# combo-03_2.net
KiCad netlist of a schematic drawn in EAGLE
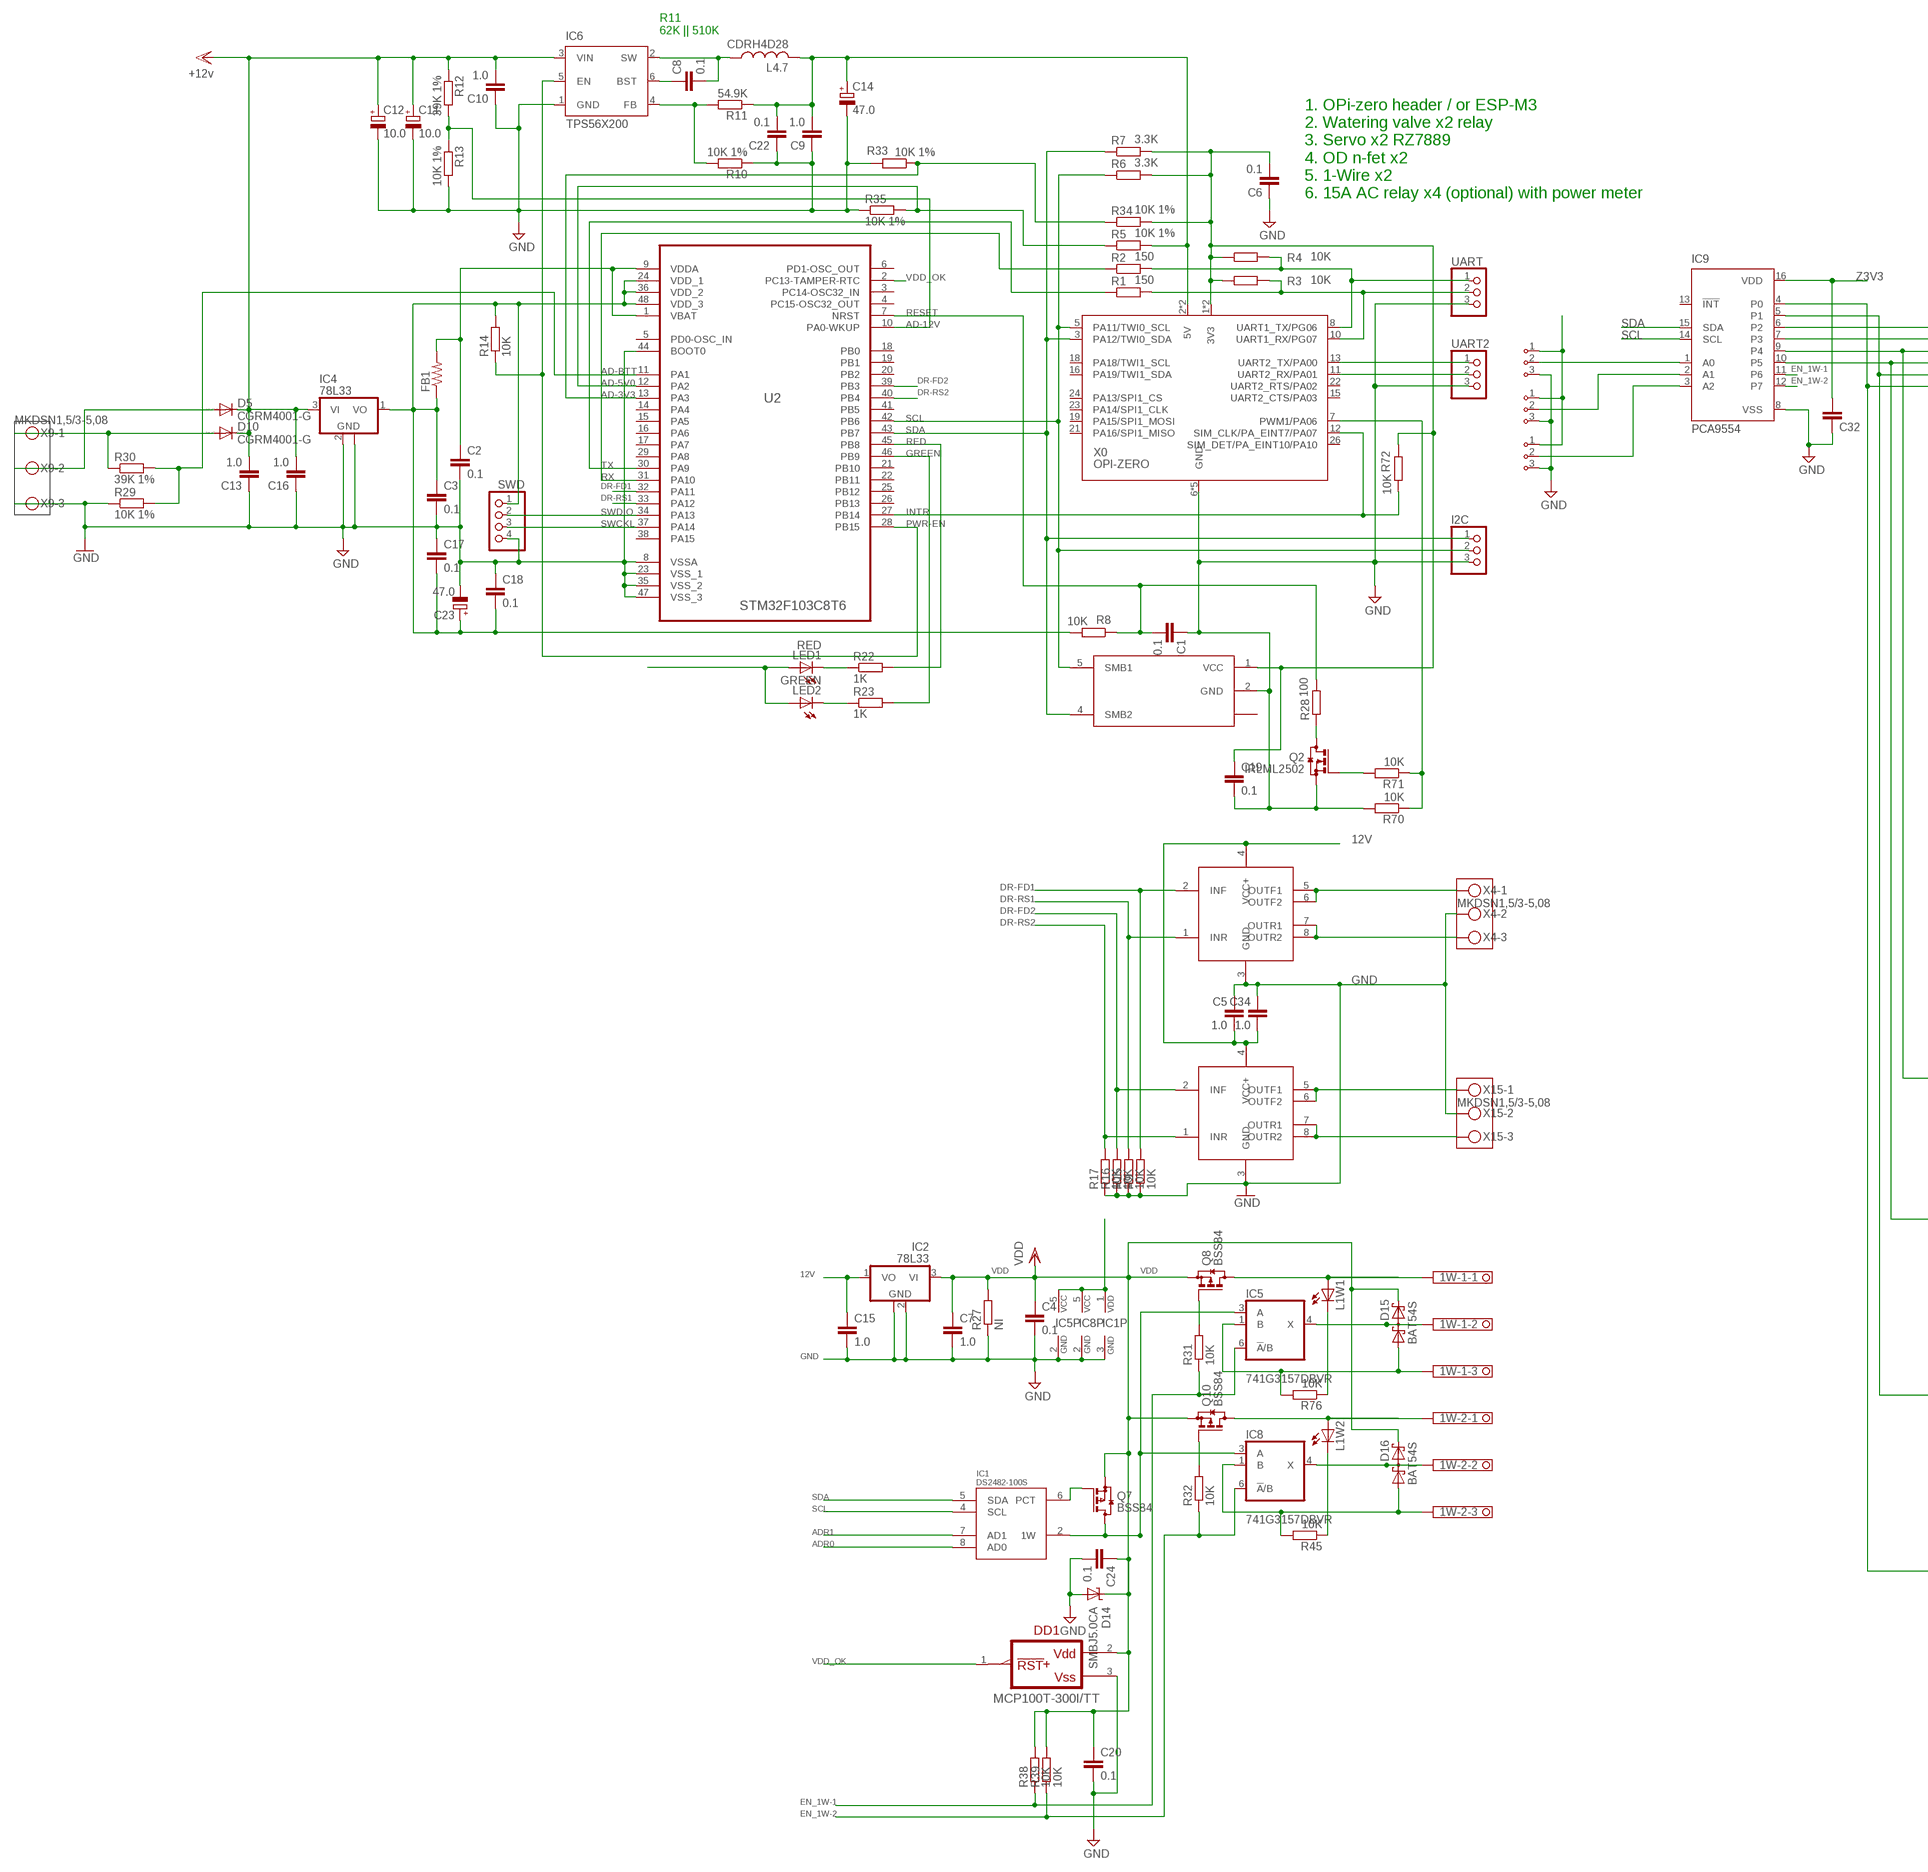
[diagram p0: schematic, sheet 1, part 1 of 2]
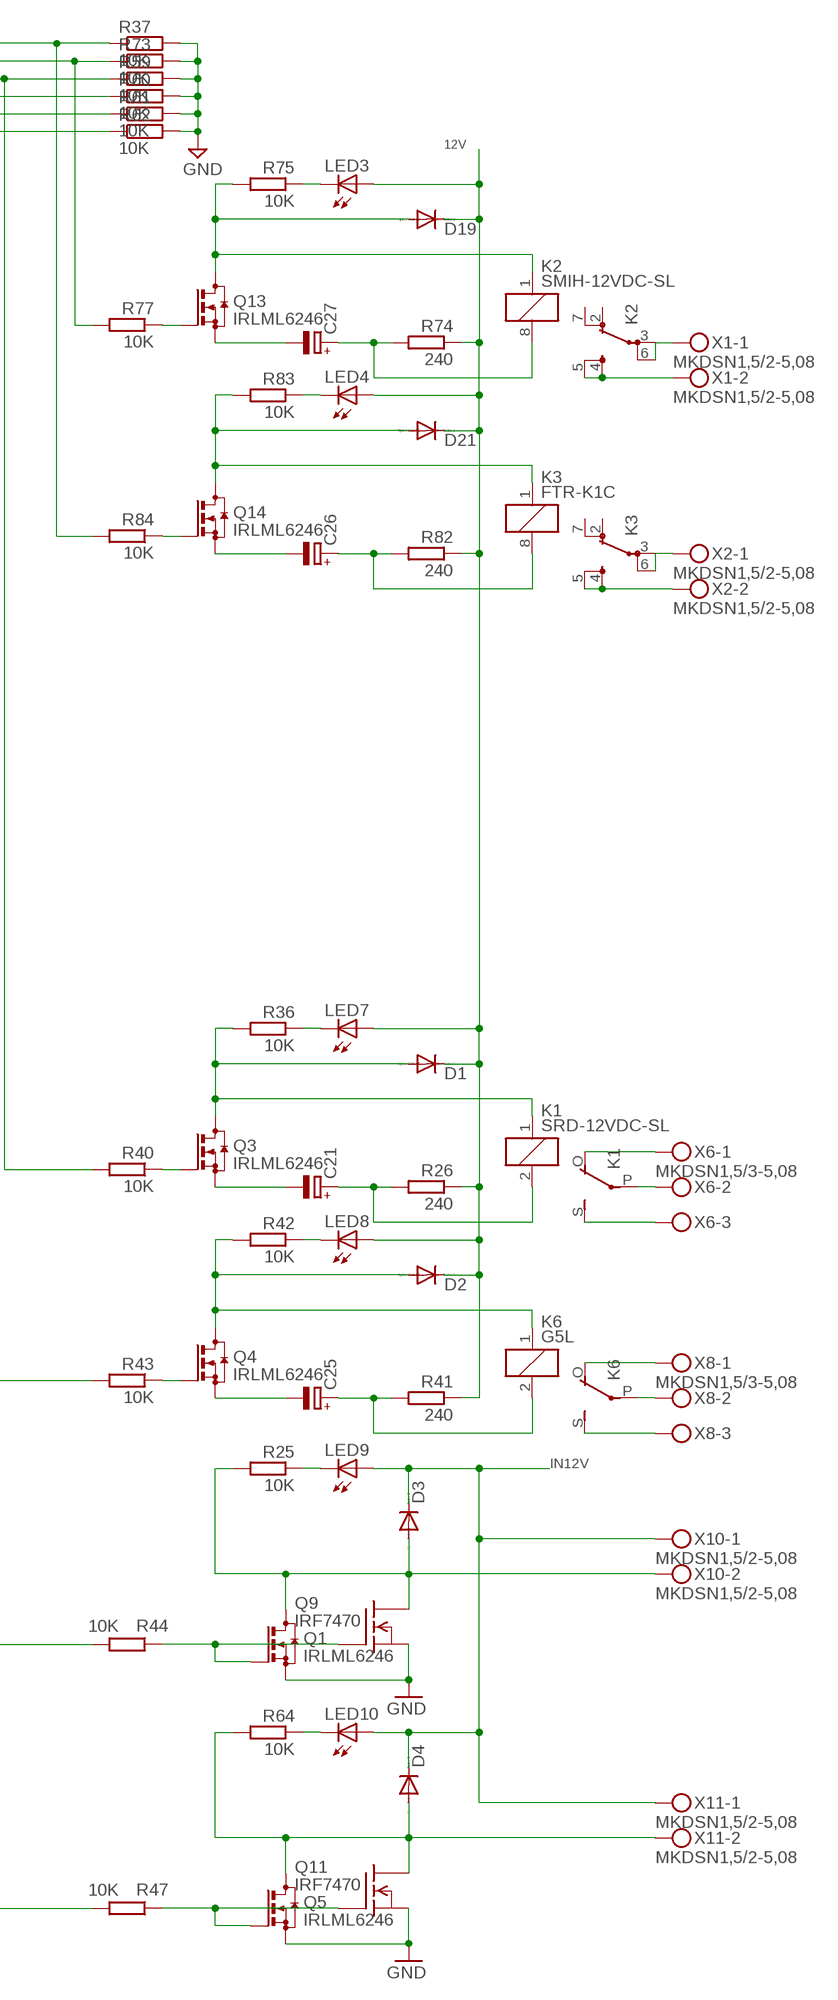
[diagram p1: schematic, sheet 1, part 2 of 2]

(export (version "E")
  (design (tool "Eeschema 10.0.6"))
  (components
    (comp (ref "1W-1")
      (value "1751251")
      (footprint "eagle-import:1751251")
      (libsource (lib "eagle-import") (part "1751251"))
    )
    (comp (ref "1W-2")
      (value "1751251")
      (footprint "eagle-import:1751251")
      (libsource (lib "eagle-import") (part "1751251"))
    )
    (comp (ref "A0")
      (value "ADDR3PIN0603")
      (footprint "eagle-import:0603-3PIN")
      (libsource (lib "eagle-import") (part "ADDR3PIN0603"))
    )
    (comp (ref "A1")
      (value "ADDR3PIN0603")
      (footprint "eagle-import:0603-3PIN")
      (libsource (lib "eagle-import") (part "ADDR3PIN0603"))
    )
    (comp (ref "A2")
      (value "ADDR3PIN0603")
      (footprint "eagle-import:0603-3PIN")
      (libsource (lib "eagle-import") (part "ADDR3PIN0603"))
    )
    (comp (ref "C1")
      (value "0.1")
      (footprint "eagle-import:C0603")
      (libsource (lib "eagle-import") (part "C-EUC0603"))
    )
    (comp (ref "C2")
      (value "0.1")
      (footprint "eagle-import:C0603")
      (libsource (lib "eagle-import") (part "C-EUC0603"))
    )
    (comp (ref "C3")
      (value "0.1")
      (footprint "eagle-import:C0603")
      (libsource (lib "eagle-import") (part "C-EUC0603"))
    )
    (comp (ref "C4")
      (value "0.1")
      (footprint "eagle-import:C0603")
      (libsource (lib "eagle-import") (part "C-EUC0603"))
    )
    (comp (ref "C5")
      (value "1.0")
      (footprint "eagle-import:C0805")
      (libsource (lib "eagle-import") (part "C-EUC0805"))
    )
    (comp (ref "C6")
      (value "0.1")
      (footprint "eagle-import:C0805")
      (libsource (lib "eagle-import") (part "C-EUC0805"))
    )
    (comp (ref "C7")
      (value "1.0")
      (footprint "eagle-import:C0805")
      (libsource (lib "eagle-import") (part "C-EUC0805"))
    )
    (comp (ref "C8")
      (value "0.1")
      (footprint "eagle-import:C0805")
      (libsource (lib "eagle-import") (part "C-EUC0805"))
    )
    (comp (ref "C9")
      (value "1.0")
      (footprint "eagle-import:C0805")
      (libsource (lib "eagle-import") (part "C-EUC0805"))
    )
    (comp (ref "C10")
      (value "1.0")
      (footprint "eagle-import:C1206")
      (libsource (lib "eagle-import") (part "C-EUC1206"))
    )
    (comp (ref "C11")
      (value "10.0")
      (footprint "eagle-import:C_6032-28R")
      (libsource (lib "eagle-import") (part "CPOL-EUC/6032-28R"))
    )
    (comp (ref "C12")
      (value "10.0")
      (footprint "eagle-import:C_6032-28R")
      (libsource (lib "eagle-import") (part "CPOL-EUC/6032-28R"))
    )
    (comp (ref "C13")
      (value "1.0")
      (footprint "eagle-import:C1206")
      (libsource (lib "eagle-import") (part "C-EUC1206"))
    )
    (comp (ref "C14")
      (value "47.0")
      (footprint "eagle-import:B_3528-21R")
      (libsource (lib "eagle-import") (part "CPOL-EUB/3528-21R"))
    )
    (comp (ref "C15")
      (value "1.0")
      (footprint "eagle-import:C0805")
      (libsource (lib "eagle-import") (part "C-EUC0805"))
    )
    (comp (ref "C16")
      (value "1.0")
      (footprint "eagle-import:C1206")
      (libsource (lib "eagle-import") (part "C-EUC1206"))
    )
    (comp (ref "C17")
      (value "0.1")
      (footprint "eagle-import:C0603")
      (libsource (lib "eagle-import") (part "C-EUC0603"))
    )
    (comp (ref "C18")
      (value "0.1")
      (footprint "eagle-import:C0603")
      (libsource (lib "eagle-import") (part "C-EUC0603"))
    )
    (comp (ref "C19")
      (value "0.1")
      (footprint "eagle-import:C0603")
      (libsource (lib "eagle-import") (part "C-EUC0603"))
    )
    (comp (ref "C20")
      (value "0.1")
      (footprint "eagle-import:C0603")
      (libsource (lib "eagle-import") (part "C-EUC0603"))
    )
    (comp (ref "C21")
      (value "CPOL-EUE3.5-8")
      (footprint "eagle-import:E3,5-8")
      (libsource (lib "eagle-import") (part "CPOL-EUE3.5-8"))
    )
    (comp (ref "C22")
      (value "0.1")
      (footprint "eagle-import:C0805")
      (libsource (lib "eagle-import") (part "C-EUC0805"))
    )
    (comp (ref "C23")
      (value "47.0")
      (footprint "eagle-import:B_3528-21R")
      (libsource (lib "eagle-import") (part "CPOL-EUB/3528-21R"))
    )
    (comp (ref "C24")
      (value "0.1")
      (footprint "eagle-import:C0603")
      (libsource (lib "eagle-import") (part "C-EUC0603"))
    )
    (comp (ref "C25")
      (value "CPOL-EUE3.5-8")
      (footprint "eagle-import:E3,5-8")
      (libsource (lib "eagle-import") (part "CPOL-EUE3.5-8"))
    )
    (comp (ref "C26")
      (value "CPOL-EUE3.5-8")
      (footprint "eagle-import:E3,5-8")
      (libsource (lib "eagle-import") (part "CPOL-EUE3.5-8"))
    )
    (comp (ref "C27")
      (value "CPOL-EUE3.5-8")
      (footprint "eagle-import:E3,5-8")
      (libsource (lib "eagle-import") (part "CPOL-EUE3.5-8"))
    )
    (comp (ref "C32")
      (value "C-EUC0805")
      (footprint "eagle-import:C0805")
      (libsource (lib "eagle-import") (part "C-EUC0805"))
    )
    (comp (ref "C34")
      (value "1.0")
      (footprint "eagle-import:C0805")
      (libsource (lib "eagle-import") (part "C-EUC0805"))
    )
    (comp (ref "D1")
      (value "DIODE-SOD123")
      (footprint "eagle-import:SOD123")
      (libsource (lib "eagle-import") (part "DIODE-SOD123"))
    )
    (comp (ref "D2")
      (value "DIODE-SOD123")
      (footprint "eagle-import:SOD123")
      (libsource (lib "eagle-import") (part "DIODE-SOD123"))
    )
    (comp (ref "D3")
      (value "DIODE-SOD123")
      (footprint "eagle-import:SOD123")
      (libsource (lib "eagle-import") (part "DIODE-SOD123"))
    )
    (comp (ref "D4")
      (value "DIODE-SOD123")
      (footprint "eagle-import:SOD123")
      (libsource (lib "eagle-import") (part "DIODE-SOD123"))
    )
    (comp (ref "D5")
      (value "CGRM4001-G")
      (footprint "eagle-import:SOD-123_MINI-SMA")
      (libsource (lib "eagle-import") (part "CGRM400-G1"))
    )
    (comp (ref "D10")
      (value "CGRM4001-G")
      (footprint "eagle-import:SOD-123_MINI-SMA")
      (libsource (lib "eagle-import") (part "CGRM400-G1"))
    )
    (comp (ref "D14")
      (value "SMBJ5.0CA")
      (footprint "eagle-import:SMBJ")
      (libsource (lib "eagle-import") (part "SUPPRESSOR-SMBJ"))
    )
    (comp (ref "D15")
      (value "BAT54S")
      (footprint "eagle-import:SOT23")
      (libsource (lib "eagle-import") (part "BAT54S"))
    )
    (comp (ref "D16")
      (value "BAT54S")
      (footprint "eagle-import:SOT23")
      (libsource (lib "eagle-import") (part "BAT54S"))
    )
    (comp (ref "D19")
      (value "DIODE-SOD123")
      (footprint "eagle-import:SOD123")
      (libsource (lib "eagle-import") (part "DIODE-SOD123"))
    )
    (comp (ref "D21")
      (value "DIODE-SOD123")
      (footprint "eagle-import:SOD123")
      (libsource (lib "eagle-import") (part "DIODE-SOD123"))
    )
    (comp (ref "DD1")
      (value "MCP100T-300I/TT")
      (footprint "eagle-import:SOT23")
      (libsource (lib "eagle-import") (part "MCP100T-300I/TT"))
    )
    (comp (ref "FB1")
      (value "R-US_R0805")
      (footprint "eagle-import:R0805")
      (libsource (lib "eagle-import") (part "R-US_R0805"))
    )
    (comp (ref "I2C")
      (value "PINHD-1X3")
      (footprint "eagle-import:1X03")
      (libsource (lib "eagle-import") (part "PINHD-1X3"))
    )
    (comp (ref "IC1")
      (value "DS2482-100S")
      (footprint "eagle-import:SO08")
      (libsource (lib "eagle-import") (part "DS2482-100S"))
    )
    (comp (ref "IC2")
      (value "78L33")
      (footprint "eagle-import:SOT89")
      (libsource (lib "eagle-import") (part "78LF05"))
    )
    (comp (ref "IC3")
      (value "RZ7889")
      (footprint "eagle-import:SO8")
      (libsource (lib "eagle-import") (part "RZ7889"))
    )
    (comp (ref "IC4")
      (value "78L33")
      (footprint "eagle-import:SOT89")
      (libsource (lib "eagle-import") (part "78LF05"))
    )
    (comp (ref "IC5")
      (value "741G3157DBVR")
      (footprint "eagle-import:DBV_R-PDSO-G6")
      (libsource (lib "eagle-import") (part "741G3157DBVR"))
    )
    (comp (ref "IC6")
      (value "TPS56X200")
      (footprint "eagle-import:TSOT23-6_DDC")
      (libsource (lib "eagle-import") (part "TPS56X200"))
    )
    (comp (ref "IC7")
      (value "LTC1694")
      (footprint "eagle-import:SOT23-5")
      (libsource (lib "eagle-import") (part "LTC1694"))
    )
    (comp (ref "IC8")
      (value "741G3157DBVR")
      (footprint "eagle-import:DBV_R-PDSO-G6")
      (libsource (lib "eagle-import") (part "741G3157DBVR"))
    )
    (comp (ref "IC9")
      (value "PCA9554")
      (footprint "eagle-import:SO16W")
      (fields (field (name "MPN") "PCF8574T/3,512"))
      (libsource (lib "eagle-import") (part "PCF8574T"))
    )
    (comp (ref "IC10")
      (value "RZ7889")
      (footprint "eagle-import:SO8")
      (libsource (lib "eagle-import") (part "RZ7889"))
    )
    (comp (ref "K1")
      (value "SRD-12VDC-SL")
      (footprint "eagle-import:G5LE")
      (libsource (lib "eagle-import") (part "G5L"))
    )
    (comp (ref "K2")
      (value "SMIH-12VDC-SL")
      (footprint "eagle-import:FTR-K1C")
      (libsource (lib "eagle-import") (part "FTR-K1C"))
    )
    (comp (ref "K3")
      (value "FTR-K1C")
      (footprint "eagle-import:FTR-K1C")
      (libsource (lib "eagle-import") (part "FTR-K1C"))
    )
    (comp (ref "K6")
      (value "G5L")
      (footprint "eagle-import:G5LE")
      (libsource (lib "eagle-import") (part "G5L"))
    )
    (comp (ref "L1W1")
      (value "LEDSMT1206")
      (footprint "eagle-import:1206")
      (libsource (lib "eagle-import") (part "LEDSMT1206"))
    )
    (comp (ref "L1W2")
      (value "LEDSMT1206")
      (footprint "eagle-import:1206")
      (libsource (lib "eagle-import") (part "LEDSMT1206"))
    )
    (comp (ref "L4.7")
      (value "CDRH4D28")
      (footprint "eagle-import:CDRH4D28")
      (libsource (lib "eagle-import") (part "CDRH4D28"))
    )
    (comp (ref "LED1")
      (value "RED")
      (footprint "eagle-import:CHIPLED_1206")
      (libsource (lib "eagle-import") (part "LEDCHIPLED_1206"))
    )
    (comp (ref "LED2")
      (value "GREEN")
      (footprint "eagle-import:CHIPLED_1206")
      (libsource (lib "eagle-import") (part "LEDCHIPLED_1206"))
    )
    (comp (ref "LED3")
      (value "LEDSMT1206")
      (footprint "eagle-import:1206")
      (libsource (lib "eagle-import") (part "LEDSMT1206"))
    )
    (comp (ref "LED4")
      (value "LEDSMT1206")
      (footprint "eagle-import:1206")
      (libsource (lib "eagle-import") (part "LEDSMT1206"))
    )
    (comp (ref "LED7")
      (value "LEDSMT1206")
      (footprint "eagle-import:1206")
      (libsource (lib "eagle-import") (part "LEDSMT1206"))
    )
    (comp (ref "LED8")
      (value "LEDSMT1206")
      (footprint "eagle-import:1206")
      (libsource (lib "eagle-import") (part "LEDSMT1206"))
    )
    (comp (ref "LED9")
      (value "LEDSMT1206")
      (footprint "eagle-import:1206")
      (libsource (lib "eagle-import") (part "LEDSMT1206"))
    )
    (comp (ref "LED10")
      (value "LEDSMT1206")
      (footprint "eagle-import:1206")
      (libsource (lib "eagle-import") (part "LEDSMT1206"))
    )
    (comp (ref "Q1")
      (value "IRLML6246")
      (footprint "eagle-import:SOT23")
      (libsource (lib "eagle-import") (part "BSS123"))
    )
    (comp (ref "Q2")
      (value "IRLML2502")
      (footprint "eagle-import:SOT23")
      (libsource (lib "eagle-import") (part "IRLML2502"))
    )
    (comp (ref "Q3")
      (value "IRLML6246")
      (footprint "eagle-import:SOT23")
      (libsource (lib "eagle-import") (part "BSS123"))
    )
    (comp (ref "Q4")
      (value "IRLML6246")
      (footprint "eagle-import:SOT23")
      (libsource (lib "eagle-import") (part "BSS123"))
    )
    (comp (ref "Q5")
      (value "IRLML6246")
      (footprint "eagle-import:SOT23")
      (libsource (lib "eagle-import") (part "BSS123"))
    )
    (comp (ref "Q7")
      (value "BSS84")
      (footprint "eagle-import:SOT23")
      (libsource (lib "eagle-import") (part "BSS84"))
    )
    (comp (ref "Q8")
      (value "BSS84")
      (footprint "eagle-import:SOT23")
      (libsource (lib "eagle-import") (part "BSS84"))
    )
    (comp (ref "Q9")
      (value "IRF7470")
      (footprint "eagle-import:SO-8")
      (libsource (lib "eagle-import") (part "FDS5680"))
    )
    (comp (ref "Q10")
      (value "BSS84")
      (footprint "eagle-import:SOT23")
      (libsource (lib "eagle-import") (part "BSS84"))
    )
    (comp (ref "Q11")
      (value "IRF7470")
      (footprint "eagle-import:SO-8")
      (libsource (lib "eagle-import") (part "FDS5680"))
    )
    (comp (ref "Q13")
      (value "IRLML6246")
      (footprint "eagle-import:SOT23")
      (libsource (lib "eagle-import") (part "BSS123"))
    )
    (comp (ref "Q14")
      (value "IRLML6246")
      (footprint "eagle-import:SOT23")
      (libsource (lib "eagle-import") (part "BSS123"))
    )
    (comp (ref "R1")
      (value "150")
      (footprint "eagle-import:R0603")
      (libsource (lib "eagle-import") (part "R-EU_R0603"))
    )
    (comp (ref "R2")
      (value "150")
      (footprint "eagle-import:R0603")
      (libsource (lib "eagle-import") (part "R-EU_R0603"))
    )
    (comp (ref "R3")
      (value "10K")
      (footprint "eagle-import:R0603")
      (libsource (lib "eagle-import") (part "R-EU_R0603"))
    )
    (comp (ref "R4")
      (value "10K")
      (footprint "eagle-import:R0603")
      (libsource (lib "eagle-import") (part "R-EU_R0603"))
    )
    (comp (ref "R5")
      (value "10K 1%")
      (footprint "eagle-import:R0603")
      (libsource (lib "eagle-import") (part "R-EU_R0603"))
    )
    (comp (ref "R6")
      (value "3.3K")
      (footprint "eagle-import:R0603")
      (libsource (lib "eagle-import") (part "R-EU_R0603"))
    )
    (comp (ref "R7")
      (value "3.3K")
      (footprint "eagle-import:R0603")
      (libsource (lib "eagle-import") (part "R-EU_R0603"))
    )
    (comp (ref "R8")
      (value "10K")
      (footprint "eagle-import:R0603")
      (libsource (lib "eagle-import") (part "R-EU_R0603"))
    )
    (comp (ref "R9")
      (value "10K")
      (footprint "eagle-import:R0603")
      (libsource (lib "eagle-import") (part "R-EU_R0603"))
    )
    (comp (ref "R10")
      (value "10K 1%")
      (footprint "eagle-import:R0603")
      (libsource (lib "eagle-import") (part "R-EU_R0603"))
    )
    (comp (ref "R11")
      (value "54.9K")
      (footprint "eagle-import:R0603")
      (libsource (lib "eagle-import") (part "R-EU_R0603"))
    )
    (comp (ref "R12")
      (value "39K 1%")
      (footprint "eagle-import:R0603")
      (libsource (lib "eagle-import") (part "R-EU_R0603"))
    )
    (comp (ref "R13")
      (value "10K 1%")
      (footprint "eagle-import:R0603")
      (libsource (lib "eagle-import") (part "R-EU_R0603"))
    )
    (comp (ref "R14")
      (value "10K")
      (footprint "eagle-import:R0603")
      (libsource (lib "eagle-import") (part "R-EU_R0603"))
    )
    (comp (ref "R15")
      (value "10K")
      (footprint "eagle-import:R0603")
      (libsource (lib "eagle-import") (part "R-EU_R0603"))
    )
    (comp (ref "R16")
      (value "10K")
      (footprint "eagle-import:R0603")
      (libsource (lib "eagle-import") (part "R-EU_R0603"))
    )
    (comp (ref "R17")
      (value "10K")
      (footprint "eagle-import:R0603")
      (libsource (lib "eagle-import") (part "R-EU_R0603"))
    )
    (comp (ref "R22")
      (value "1K")
      (footprint "eagle-import:R0603")
      (libsource (lib "eagle-import") (part "R-EU_R0603"))
    )
    (comp (ref "R23")
      (value "1K")
      (footprint "eagle-import:R0603")
      (libsource (lib "eagle-import") (part "R-EU_R0603"))
    )
    (comp (ref "R25")
      (value "10K")
      (footprint "eagle-import:R0603")
      (libsource (lib "eagle-import") (part "R-EU_R0603"))
    )
    (comp (ref "R26")
      (value "240")
      (footprint "eagle-import:R1206")
      (libsource (lib "eagle-import") (part "R-EU_R1206"))
    )
    (comp (ref "R27")
      (value "NI")
      (footprint "eagle-import:R0603")
      (libsource (lib "eagle-import") (part "R-EU_R0603"))
    )
    (comp (ref "R28")
      (value "100")
      (footprint "eagle-import:R0603")
      (libsource (lib "eagle-import") (part "R-EU_R0603"))
    )
    (comp (ref "R29")
      (value "10K 1%")
      (footprint "eagle-import:R0603")
      (libsource (lib "eagle-import") (part "R-EU_R0603"))
    )
    (comp (ref "R30")
      (value "39K 1%")
      (footprint "eagle-import:R0603")
      (libsource (lib "eagle-import") (part "R-EU_R0603"))
    )
    (comp (ref "R31")
      (value "10K")
      (footprint "eagle-import:R0603")
      (libsource (lib "eagle-import") (part "R-EU_R0603"))
    )
    (comp (ref "R32")
      (value "10K")
      (footprint "eagle-import:R0603")
      (libsource (lib "eagle-import") (part "R-EU_R0603"))
    )
    (comp (ref "R33")
      (value "10K 1%")
      (footprint "eagle-import:R0603")
      (libsource (lib "eagle-import") (part "R-EU_R0603"))
    )
    (comp (ref "R34")
      (value "10K 1%")
      (footprint "eagle-import:R0603")
      (libsource (lib "eagle-import") (part "R-EU_R0603"))
    )
    (comp (ref "R35")
      (value "10K 1%")
      (footprint "eagle-import:R0603")
      (libsource (lib "eagle-import") (part "R-EU_R0603"))
    )
    (comp (ref "R36")
      (value "10K")
      (footprint "eagle-import:R0603")
      (libsource (lib "eagle-import") (part "R-EU_R0603"))
    )
    (comp (ref "R37")
      (value "10K")
      (footprint "eagle-import:R0603")
      (libsource (lib "eagle-import") (part "R-EU_R0603"))
    )
    (comp (ref "R38")
      (value "10K")
      (footprint "eagle-import:R0603")
      (libsource (lib "eagle-import") (part "R-EU_R0603"))
    )
    (comp (ref "R39")
      (value "10K")
      (footprint "eagle-import:R0603")
      (libsource (lib "eagle-import") (part "R-EU_R0603"))
    )
    (comp (ref "R40")
      (value "10K")
      (footprint "eagle-import:R0603")
      (libsource (lib "eagle-import") (part "R-EU_R0603"))
    )
    (comp (ref "R41")
      (value "240")
      (footprint "eagle-import:R1206")
      (libsource (lib "eagle-import") (part "R-EU_R1206"))
    )
    (comp (ref "R42")
      (value "10K")
      (footprint "eagle-import:R0603")
      (libsource (lib "eagle-import") (part "R-EU_R0603"))
    )
    (comp (ref "R43")
      (value "10K")
      (footprint "eagle-import:R0603")
      (libsource (lib "eagle-import") (part "R-EU_R0603"))
    )
    (comp (ref "R44")
      (value "10K")
      (footprint "eagle-import:R0603")
      (libsource (lib "eagle-import") (part "R-EU_R0603"))
    )
    (comp (ref "R45")
      (value "10K")
      (footprint "eagle-import:R0603")
      (libsource (lib "eagle-import") (part "R-EU_R0603"))
    )
    (comp (ref "R47")
      (value "10K")
      (footprint "eagle-import:R0603")
      (libsource (lib "eagle-import") (part "R-EU_R0603"))
    )
    (comp (ref "R59")
      (value "10K")
      (footprint "eagle-import:R0603")
      (libsource (lib "eagle-import") (part "R-EU_R0603"))
    )
    (comp (ref "R60")
      (value "10K")
      (footprint "eagle-import:R0603")
      (libsource (lib "eagle-import") (part "R-EU_R0603"))
    )
    (comp (ref "R61")
      (value "10K")
      (footprint "eagle-import:R0603")
      (libsource (lib "eagle-import") (part "R-EU_R0603"))
    )
    (comp (ref "R62")
      (value "10K")
      (footprint "eagle-import:R0603")
      (libsource (lib "eagle-import") (part "R-EU_R0603"))
    )
    (comp (ref "R64")
      (value "10K")
      (footprint "eagle-import:R0603")
      (libsource (lib "eagle-import") (part "R-EU_R0603"))
    )
    (comp (ref "R70")
      (value "10K")
      (footprint "eagle-import:R0603")
      (libsource (lib "eagle-import") (part "R-EU_R0603"))
    )
    (comp (ref "R71")
      (value "10K")
      (footprint "eagle-import:R0603")
      (libsource (lib "eagle-import") (part "R-EU_R0603"))
    )
    (comp (ref "R72")
      (value "10K")
      (footprint "eagle-import:R0603")
      (libsource (lib "eagle-import") (part "R-EU_R0603"))
    )
    (comp (ref "R73")
      (value "10K")
      (footprint "eagle-import:R0603")
      (libsource (lib "eagle-import") (part "R-EU_R0603"))
    )
    (comp (ref "R74")
      (value "240")
      (footprint "eagle-import:R1206")
      (libsource (lib "eagle-import") (part "R-EU_R1206"))
    )
    (comp (ref "R75")
      (value "10K")
      (footprint "eagle-import:R0603")
      (libsource (lib "eagle-import") (part "R-EU_R0603"))
    )
    (comp (ref "R76")
      (value "10K")
      (footprint "eagle-import:R0603")
      (libsource (lib "eagle-import") (part "R-EU_R0603"))
    )
    (comp (ref "R77")
      (value "10K")
      (footprint "eagle-import:R0603")
      (libsource (lib "eagle-import") (part "R-EU_R0603"))
    )
    (comp (ref "R82")
      (value "240")
      (footprint "eagle-import:R1206")
      (libsource (lib "eagle-import") (part "R-EU_R1206"))
    )
    (comp (ref "R83")
      (value "10K")
      (footprint "eagle-import:R0603")
      (libsource (lib "eagle-import") (part "R-EU_R0603"))
    )
    (comp (ref "R84")
      (value "10K")
      (footprint "eagle-import:R0603")
      (libsource (lib "eagle-import") (part "R-EU_R0603"))
    )
    (comp (ref "SWD")
      (value "PINHD-1X4")
      (footprint "eagle-import:1X04")
      (libsource (lib "eagle-import") (part "PINHD-1X4"))
    )
    (comp (ref "U2")
      (value "STM32F103C8T6")
      (footprint "eagle-import:QFP50P900X900X160-48N")
      (fields (field (name "MPN") "STM32F100CBT6B"))
      (libsource (lib "eagle-import") (part "STM32F100CBT6B"))
    )
    (comp (ref "UART")
      (value "PINHD-1X3")
      (footprint "eagle-import:1X03")
      (libsource (lib "eagle-import") (part "PINHD-1X3"))
    )
    (comp (ref "UART2")
      (value "PINHD-1X3")
      (footprint "eagle-import:1X03")
      (libsource (lib "eagle-import") (part "PINHD-1X3"))
    )
    (comp (ref "X0")
      (value "OPI-ZERO")
      (footprint "eagle-import:OPI0")
      (libsource (lib "eagle-import") (part "OPI-ZERO"))
    )
    (comp (ref "X1")
      (value "MKDSN1,5/2-5,08")
      (footprint "eagle-import:MKDSN1,5_2-5,08")
      (libsource (lib "eagle-import") (part "MKDSN1,5/2-5,08"))
    )
    (comp (ref "X2")
      (value "MKDSN1,5/2-5,08")
      (footprint "eagle-import:MKDSN1,5_2-5,08")
      (libsource (lib "eagle-import") (part "MKDSN1,5/2-5,08"))
    )
    (comp (ref "X4")
      (value "MKDSN1,5/3-5,08")
      (footprint "eagle-import:MKDSN1,5_3-5,08")
      (libsource (lib "eagle-import") (part "MKDSN1,5/3-5,08"))
    )
    (comp (ref "X6")
      (value "MKDSN1,5/3-5,08")
      (footprint "eagle-import:MKDSN1,5_3-5,08")
      (libsource (lib "eagle-import") (part "MKDSN1,5/3-5,08"))
    )
    (comp (ref "X8")
      (value "MKDSN1,5/3-5,08")
      (footprint "eagle-import:MKDSN1,5_3-5,08")
      (libsource (lib "eagle-import") (part "MKDSN1,5/3-5,08"))
    )
    (comp (ref "X9")
      (value "MKDSN1,5/3-5,08")
      (footprint "eagle-import:MKDSN1,5_3-5,08")
      (libsource (lib "eagle-import") (part "MKDSN1,5/3-5,08"))
    )
    (comp (ref "X10")
      (value "MKDSN1,5/2-5,08")
      (footprint "eagle-import:MKDSN1,5_2-5,08")
      (libsource (lib "eagle-import") (part "MKDSN1,5/2-5,08"))
    )
    (comp (ref "X11")
      (value "MKDSN1,5/2-5,08")
      (footprint "eagle-import:MKDSN1,5_2-5,08")
      (libsource (lib "eagle-import") (part "MKDSN1,5/2-5,08"))
    )
    (comp (ref "X15")
      (value "MKDSN1,5/3-5,08")
      (footprint "eagle-import:MKDSN1,5_3-5,08")
      (libsource (lib "eagle-import") (part "MKDSN1,5/3-5,08"))
    )
  )
  (nets
    (net (code "1") (name "+12v") (class "Default")
      (node (ref "C10") (pin "2") (pinfunction "2_2") (pintype "passive"))
      (node (ref "C11") (pin "+") (pinfunction "+_+") (pintype "passive"))
      (node (ref "C12") (pin "+") (pinfunction "+_+") (pintype "passive"))
      (node (ref "C13") (pin "2") (pinfunction "2_2") (pintype "passive"))
      (node (ref "C15") (pin "1") (pinfunction "1_1") (pintype "passive"))
      (node (ref "C16") (pin "2") (pinfunction "2_2") (pintype "passive"))
      (node (ref "C34") (pin "2") (pinfunction "2_2") (pintype "passive"))
      (node (ref "C5") (pin "2") (pinfunction "2_2") (pintype "passive"))
      (node (ref "D1") (pin "C") (pinfunction "C_C") (pintype "passive"))
      (node (ref "D10") (pin "C") (pinfunction "C_C") (pintype "passive"))
      (node (ref "D19") (pin "C") (pinfunction "C_C") (pintype "passive"))
      (node (ref "D2") (pin "C") (pinfunction "C_C") (pintype "passive"))
      (node (ref "D21") (pin "C") (pinfunction "C_C") (pintype "passive"))
      (node (ref "D5") (pin "C") (pinfunction "C_C") (pintype "passive"))
      (node (ref "IC10") (pin "4") (pinfunction "VCC+_4") (pintype "bidirectional"))
      (node (ref "IC2") (pin "1") (pinfunction "VO_1") (pintype "passive"))
      (node (ref "IC3") (pin "4") (pinfunction "VCC+_4") (pintype "bidirectional"))
      (node (ref "IC4") (pin "3") (pinfunction "VI_3") (pintype "input"))
      (node (ref "IC6") (pin "3") (pinfunction "VIN_3") (pintype "input"))
      (node (ref "LED3") (pin "A") (pinfunction "A_A") (pintype "passive"))
      (node (ref "LED4") (pin "A") (pinfunction "A_A") (pintype "passive"))
      (node (ref "LED7") (pin "A") (pinfunction "A_A") (pintype "passive"))
      (node (ref "LED8") (pin "A") (pinfunction "A_A") (pintype "passive"))
      (node (ref "R12") (pin "1") (pinfunction "1_1") (pintype "passive"))
      (node (ref "R26") (pin "1") (pinfunction "1_1") (pintype "passive"))
      (node (ref "R41") (pin "1") (pinfunction "1_1") (pintype "passive"))
      (node (ref "R74") (pin "1") (pinfunction "1_1") (pintype "passive"))
      (node (ref "R82") (pin "1") (pinfunction "1_1") (pintype "passive"))
    )
    (net (code "2") (name "/AD-3V3") (class "Default")
      (node (ref "R33") (pin "1") (pinfunction "1_1") (pintype "passive"))
      (node (ref "R34") (pin "1") (pinfunction "1_1") (pintype "passive"))
      (node (ref "U2") (pin "13") (pinfunction "PA3_13") (pintype "bidirectional"))
    )
    (net (code "3") (name "/AD-5V0") (class "Default")
      (node (ref "R35") (pin "2") (pinfunction "2_2") (pintype "passive"))
      (node (ref "R5") (pin "1") (pinfunction "1_1") (pintype "passive"))
      (node (ref "U2") (pin "12") (pinfunction "PA2_12") (pintype "bidirectional"))
    )
    (net (code "4") (name "/AD-12V") (class "Default")
      (node (ref "R12") (pin "2") (pinfunction "2_2") (pintype "passive"))
      (node (ref "R13") (pin "1") (pinfunction "1_1") (pintype "passive"))
      (node (ref "U2") (pin "10") (pinfunction "PA0-WKUP_10") (pintype "bidirectional"))
    )
    (net (code "5") (name "/AD-BTT") (class "Default")
      (node (ref "R29") (pin "2") (pinfunction "2_2") (pintype "passive"))
      (node (ref "R30") (pin "2") (pinfunction "2_2") (pintype "passive"))
      (node (ref "U2") (pin "11") (pinfunction "PA1_11") (pintype "bidirectional"))
    )
    (net (code "6") (name "/ADR0") (class "Default")
      (node (ref "A2") (pin "2") (pinfunction "P$1_2") (pintype "bidirectional"))
      (node (ref "IC1") (pin "8") (pinfunction "AD0_8") (pintype "input"))
      (node (ref "IC9") (pin "1") (pinfunction "A0_1") (pintype "input"))
    )
    (net (code "7") (name "/ADR1") (class "Default")
      (node (ref "A1") (pin "2") (pinfunction "P$1_2") (pintype "bidirectional"))
      (node (ref "IC1") (pin "7") (pinfunction "AD1_7") (pintype "input"))
      (node (ref "IC9") (pin "2") (pinfunction "A1_2") (pintype "input"))
    )
    (net (code "8") (name "/DR-FD1") (class "Default")
      (node (ref "IC3") (pin "2") (pinfunction "INF_2") (pintype "bidirectional"))
      (node (ref "R9") (pin "2") (pinfunction "2_2") (pintype "passive"))
      (node (ref "U2") (pin "32") (pinfunction "PA11_32") (pintype "bidirectional"))
    )
    (net (code "9") (name "/DR-FD2") (class "Default")
      (node (ref "IC10") (pin "2") (pinfunction "INF_2") (pintype "bidirectional"))
      (node (ref "R16") (pin "2") (pinfunction "2_2") (pintype "passive"))
      (node (ref "U2") (pin "39") (pinfunction "PB3_39") (pintype "bidirectional"))
    )
    (net (code "10") (name "/DR-RS1") (class "Default")
      (node (ref "IC3") (pin "1") (pinfunction "INR_1") (pintype "bidirectional"))
      (node (ref "R15") (pin "2") (pinfunction "2_2") (pintype "passive"))
      (node (ref "U2") (pin "33") (pinfunction "PA12_33") (pintype "bidirectional"))
    )
    (net (code "11") (name "/DR-RS2") (class "Default")
      (node (ref "IC10") (pin "1") (pinfunction "INR_1") (pintype "bidirectional"))
      (node (ref "R17") (pin "2") (pinfunction "2_2") (pintype "passive"))
      (node (ref "U2") (pin "40") (pinfunction "PB4_40") (pintype "bidirectional"))
    )
    (net (code "12") (name "/EN_1W-1") (class "Default")
      (node (ref "IC5") (pin "6") (pinfunction "~{A}/B_6") (pintype "input"))
      (node (ref "IC9") (pin "11") (pinfunction "P6_11") (pintype "bidirectional"))
      (node (ref "R31") (pin "1") (pinfunction "1_1") (pintype "passive"))
      (node (ref "R38") (pin "1") (pinfunction "1_1") (pintype "passive"))
    )
    (net (code "13") (name "/EN_1W-2") (class "Default")
      (node (ref "IC8") (pin "6") (pinfunction "~{A}/B_6") (pintype "input"))
      (node (ref "IC9") (pin "12") (pinfunction "P7_12") (pintype "bidirectional"))
      (node (ref "R32") (pin "1") (pinfunction "1_1") (pintype "passive"))
      (node (ref "R39") (pin "1") (pinfunction "1_1") (pintype "passive"))
    )
    (net (code "14") (name "/GREEN") (class "Default")
      (node (ref "R23") (pin "2") (pinfunction "2_2") (pintype "passive"))
      (node (ref "U2") (pin "46") (pinfunction "PB9_46") (pintype "bidirectional"))
    )
    (net (code "15") (name "/IN12V") (class "Default")
      (node (ref "D3") (pin "C") (pinfunction "C_C") (pintype "passive"))
      (node (ref "D4") (pin "C") (pinfunction "C_C") (pintype "passive"))
      (node (ref "D5") (pin "A") (pinfunction "A_A") (pintype "passive"))
      (node (ref "LED10") (pin "A") (pinfunction "A_A") (pintype "passive"))
      (node (ref "LED9") (pin "A") (pinfunction "A_A") (pintype "passive"))
      (node (ref "X10") (pin "1") (pinfunction "KL_1") (pintype "passive"))
      (node (ref "X11") (pin "1") (pinfunction "KL_1") (pintype "passive"))
      (node (ref "X9") (pin "2") (pinfunction "KL_2") (pintype "passive"))
    )
    (net (code "16") (name "/INTR") (class "Default")
      (node (ref "R72") (pin "2") (pinfunction "2_2") (pintype "passive"))
      (node (ref "U2") (pin "27") (pinfunction "PB14_27") (pintype "bidirectional"))
      (node (ref "X0") (pin "12") (pinfunction "SIM_CLK/PA_EINT7/PA07_12") (pintype "bidirectional"))
    )
    (net (code "17") (name "/PWR-EN") (class "Default")
      (node (ref "IC6") (pin "5") (pinfunction "EN_5") (pintype "input"))
      (node (ref "R14") (pin "1") (pinfunction "1_1") (pintype "passive"))
      (node (ref "U2") (pin "28") (pinfunction "PB15_28") (pintype "bidirectional"))
    )
    (net (code "18") (name "/RED") (class "Default")
      (node (ref "R22") (pin "2") (pinfunction "2_2") (pintype "passive"))
      (node (ref "U2") (pin "45") (pinfunction "PB8_45") (pintype "bidirectional"))
    )
    (net (code "19") (name "/RESET") (class "Default")
      (node (ref "C1") (pin "2") (pinfunction "2_2") (pintype "passive"))
      (node (ref "R28") (pin "2") (pinfunction "2_2") (pintype "passive"))
      (node (ref "R8") (pin "1") (pinfunction "1_1") (pintype "passive"))
      (node (ref "U2") (pin "7") (pinfunction "NRST_7") (pintype "bidirectional"))
    )
    (net (code "20") (name "/RX") (class "Default")
      (node (ref "R2") (pin "1") (pinfunction "1_1") (pintype "passive"))
      (node (ref "U2") (pin "31") (pinfunction "PA10_31") (pintype "bidirectional"))
    )
    (net (code "21") (name "/SCL") (class "Default")
      (node (ref "I2C") (pin "2") (pinfunction "2_2") (pintype "passive"))
      (node (ref "IC1") (pin "4") (pinfunction "SCL_4") (pintype "input"))
      (node (ref "IC7") (pin "5") (pinfunction "SMB1_5") (pintype "bidirectional"))
      (node (ref "IC9") (pin "14") (pinfunction "SCL_14") (pintype "input"))
      (node (ref "R6") (pin "1") (pinfunction "1_1") (pintype "passive"))
      (node (ref "U2") (pin "42") (pinfunction "PB6_42") (pintype "bidirectional"))
      (node (ref "X0") (pin "5") (pinfunction "PA11/TWI0_SCL_5") (pintype "bidirectional"))
    )
    (net (code "22") (name "/SDA") (class "Default")
      (node (ref "I2C") (pin "1") (pinfunction "1_1") (pintype "passive"))
      (node (ref "IC1") (pin "5") (pinfunction "SDA_5") (pintype "bidirectional"))
      (node (ref "IC7") (pin "4") (pinfunction "SMB2_4") (pintype "bidirectional"))
      (node (ref "IC9") (pin "15") (pinfunction "SDA_15") (pintype "bidirectional"))
      (node (ref "R7") (pin "1") (pinfunction "1_1") (pintype "passive"))
      (node (ref "U2") (pin "43") (pinfunction "PB7_43") (pintype "bidirectional"))
      (node (ref "X0") (pin "3") (pinfunction "PA12/TWI0_SDA_3") (pintype "bidirectional"))
    )
    (net (code "23") (name "/SWCKL") (class "Default")
      (node (ref "SWD") (pin "3") (pinfunction "3_3") (pintype "passive"))
      (node (ref "U2") (pin "37") (pinfunction "PA14_37") (pintype "bidirectional"))
    )
    (net (code "24") (name "/SWDIO") (class "Default")
      (node (ref "SWD") (pin "2") (pinfunction "2_2") (pintype "passive"))
      (node (ref "U2") (pin "34") (pinfunction "PA13_34") (pintype "bidirectional"))
    )
    (net (code "25") (name "/TX") (class "Default")
      (node (ref "R1") (pin "1") (pinfunction "1_1") (pintype "passive"))
      (node (ref "U2") (pin "30") (pinfunction "PA9_30") (pintype "bidirectional"))
    )
    (net (code "26") (name "/VDD_OK") (class "Default")
      (node (ref "DD1") (pin "1") (pinfunction "~{RST}_1") (pintype "passive"))
      (node (ref "U2") (pin "2") (pinfunction "PC13-TAMPER-RTC_2") (pintype "bidirectional"))
    )
    (net (code "27") (name "/Z3V3") (class "Default")
      (node (ref "A0") (pin "1") (pinfunction "P$2_1") (pintype "power_in"))
      (node (ref "A1") (pin "1") (pinfunction "P$2_1") (pintype "power_in"))
      (node (ref "A2") (pin "1") (pinfunction "P$2_1") (pintype "power_in"))
      (node (ref "C19") (pin "1") (pinfunction "1_1") (pintype "passive"))
      (node (ref "C32") (pin "2") (pinfunction "2_2") (pintype "passive"))
      (node (ref "C6") (pin "2") (pinfunction "2_2") (pintype "passive"))
      (node (ref "IC1") (pin "1") (pinfunction "VDD_1") (pintype "power_in"))
      (node (ref "IC5") (pin "5") (pinfunction "VCC_5") (pintype "power_in"))
      (node (ref "IC7") (pin "1") (pinfunction "VCC_1") (pintype "power_in"))
      (node (ref "IC8") (pin "5") (pinfunction "VCC_5") (pintype "power_in"))
      (node (ref "IC9") (pin "16") (pinfunction "VDD_16") (pintype "power_in"))
      (node (ref "R3") (pin "1") (pinfunction "1_1") (pintype "passive"))
      (node (ref "R34") (pin "2") (pinfunction "2_2") (pintype "passive"))
      (node (ref "R4") (pin "1") (pinfunction "1_1") (pintype "passive"))
      (node (ref "R6") (pin "2") (pinfunction "2_2") (pintype "passive"))
      (node (ref "R7") (pin "2") (pinfunction "2_2") (pintype "passive"))
      (node (ref "R72") (pin "1") (pinfunction "1_1") (pintype "passive"))
      (node (ref "X0") (pin "1") (pinfunction "3V3_1") (pintype "power_in"))
      (node (ref "X0") (pin "17") (pinfunction "3V3_17") (pintype "power_in"))
    )
    (net (code "28") (name "GND") (class "Default")
      (node (ref "1W-1") (pin "3") (pinfunction "K_3") (pintype "passive"))
      (node (ref "1W-2") (pin "3") (pinfunction "K_3") (pintype "passive"))
      (node (ref "A0") (pin "3") (pinfunction "P$3_3") (pintype "power_in"))
      (node (ref "A1") (pin "3") (pinfunction "P$3_3") (pintype "power_in"))
      (node (ref "A2") (pin "3") (pinfunction "P$3_3") (pintype "power_in"))
      (node (ref "C1") (pin "1") (pinfunction "1_1") (pintype "passive"))
      (node (ref "C10") (pin "1") (pinfunction "1_1") (pintype "passive"))
      (node (ref "C11") (pin "-") (pinfunction "-_-") (pintype "passive"))
      (node (ref "C12") (pin "-") (pinfunction "-_-") (pintype "passive"))
      (node (ref "C13") (pin "1") (pinfunction "1_1") (pintype "passive"))
      (node (ref "C14") (pin "-") (pinfunction "-_-") (pintype "passive"))
      (node (ref "C15") (pin "2") (pinfunction "2_2") (pintype "passive"))
      (node (ref "C16") (pin "1") (pinfunction "1_1") (pintype "passive"))
      (node (ref "C17") (pin "1") (pinfunction "1_1") (pintype "passive"))
      (node (ref "C18") (pin "1") (pinfunction "1_1") (pintype "passive"))
      (node (ref "C19") (pin "2") (pinfunction "2_2") (pintype "passive"))
      (node (ref "C2") (pin "2") (pinfunction "2_2") (pintype "passive"))
      (node (ref "C20") (pin "2") (pinfunction "2_2") (pintype "passive"))
      (node (ref "C21") (pin "-") (pinfunction "-_-") (pintype "passive"))
      (node (ref "C22") (pin "1") (pinfunction "1_1") (pintype "passive"))
      (node (ref "C23") (pin "-") (pinfunction "-_-") (pintype "passive"))
      (node (ref "C24") (pin "2") (pinfunction "2_2") (pintype "passive"))
      (node (ref "C25") (pin "-") (pinfunction "-_-") (pintype "passive"))
      (node (ref "C26") (pin "-") (pinfunction "-_-") (pintype "passive"))
      (node (ref "C27") (pin "-") (pinfunction "-_-") (pintype "passive"))
      (node (ref "C3") (pin "2") (pinfunction "2_2") (pintype "passive"))
      (node (ref "C32") (pin "1") (pinfunction "1_1") (pintype "passive"))
      (node (ref "C34") (pin "1") (pinfunction "1_1") (pintype "passive"))
      (node (ref "C4") (pin "2") (pinfunction "2_2") (pintype "passive"))
      (node (ref "C5") (pin "1") (pinfunction "1_1") (pintype "passive"))
      (node (ref "C6") (pin "1") (pinfunction "1_1") (pintype "passive"))
      (node (ref "C7") (pin "2") (pinfunction "2_2") (pintype "passive"))
      (node (ref "C9") (pin "1") (pinfunction "1_1") (pintype "passive"))
      (node (ref "D14") (pin "A") (pinfunction "A_A") (pintype "passive"))
      (node (ref "D15") (pin "1") (pinfunction "A1_1") (pintype "passive"))
      (node (ref "D16") (pin "1") (pinfunction "A1_1") (pintype "passive"))
      (node (ref "DD1") (pin "3") (pinfunction "VSS_3") (pintype "passive"))
      (node (ref "I2C") (pin "3") (pinfunction "3_3") (pintype "passive"))
      (node (ref "IC1") (pin "3") (pinfunction "GND_3") (pintype "power_in"))
      (node (ref "IC10") (pin "3") (pinfunction "GND_3") (pintype "bidirectional"))
      (node (ref "IC2") (pin "2") (pinfunction "GND_2") (pintype "passive"))
      (node (ref "IC2") (pin "2@1") (pinfunction "GND_2@1") (pintype "passive"))
      (node (ref "IC3") (pin "3") (pinfunction "GND_3") (pintype "bidirectional"))
      (node (ref "IC4") (pin "2") (pinfunction "GND_2") (pintype "passive"))
      (node (ref "IC4") (pin "2@1") (pinfunction "GND_2@1") (pintype "passive"))
      (node (ref "IC5") (pin "1") (pinfunction "B_1") (pintype "bidirectional"))
      (node (ref "IC5") (pin "2") (pinfunction "GND_2") (pintype "power_in"))
      (node (ref "IC6") (pin "1") (pinfunction "GND_1") (pintype "power_in"))
      (node (ref "IC7") (pin "2") (pinfunction "GND_2") (pintype "power_in"))
      (node (ref "IC8") (pin "1") (pinfunction "B_1") (pintype "bidirectional"))
      (node (ref "IC8") (pin "2") (pinfunction "GND_2") (pintype "power_in"))
      (node (ref "IC9") (pin "8") (pinfunction "VSS_8") (pintype "power_in"))
      (node (ref "Q1") (pin "2") (pinfunction "S_2") (pintype "passive"))
      (node (ref "Q11") (pin "1") (pinfunction "S_1") (pintype "passive"))
      (node (ref "Q11") (pin "2") (pinfunction "S_2") (pintype "passive"))
      (node (ref "Q11") (pin "3") (pinfunction "S_3") (pintype "passive"))
      (node (ref "Q13") (pin "2") (pinfunction "S_2") (pintype "passive"))
      (node (ref "Q14") (pin "2") (pinfunction "S_2") (pintype "passive"))
      (node (ref "Q2") (pin "2") (pinfunction "S_2") (pintype "passive"))
      (node (ref "Q3") (pin "2") (pinfunction "S_2") (pintype "passive"))
      (node (ref "Q4") (pin "2") (pinfunction "S_2") (pintype "passive"))
      (node (ref "Q5") (pin "2") (pinfunction "S_2") (pintype "passive"))
      (node (ref "Q9") (pin "1") (pinfunction "S_1") (pintype "passive"))
      (node (ref "Q9") (pin "2") (pinfunction "S_2") (pintype "passive"))
      (node (ref "Q9") (pin "3") (pinfunction "S_3") (pintype "passive"))
      (node (ref "R10") (pin "1") (pinfunction "1_1") (pintype "passive"))
      (node (ref "R13") (pin "2") (pinfunction "2_2") (pintype "passive"))
      (node (ref "R15") (pin "1") (pinfunction "1_1") (pintype "passive"))
      (node (ref "R16") (pin "1") (pinfunction "1_1") (pintype "passive"))
      (node (ref "R17") (pin "1") (pinfunction "1_1") (pintype "passive"))
      (node (ref "R27") (pin "1") (pinfunction "1_1") (pintype "passive"))
      (node (ref "R29") (pin "1") (pinfunction "1_1") (pintype "passive"))
      (node (ref "R33") (pin "2") (pinfunction "2_2") (pintype "passive"))
      (node (ref "R35") (pin "1") (pinfunction "1_1") (pintype "passive"))
      (node (ref "R37") (pin "2") (pinfunction "2_2") (pintype "passive"))
      (node (ref "R45") (pin "2") (pinfunction "2_2") (pintype "passive"))
      (node (ref "R59") (pin "2") (pinfunction "2_2") (pintype "passive"))
      (node (ref "R60") (pin "2") (pinfunction "2_2") (pintype "passive"))
      (node (ref "R61") (pin "2") (pinfunction "2_2") (pintype "passive"))
      (node (ref "R62") (pin "2") (pinfunction "2_2") (pintype "passive"))
      (node (ref "R70") (pin "2") (pinfunction "2_2") (pintype "passive"))
      (node (ref "R73") (pin "2") (pinfunction "2_2") (pintype "passive"))
      (node (ref "R76") (pin "2") (pinfunction "2_2") (pintype "passive"))
      (node (ref "R9") (pin "1") (pinfunction "1_1") (pintype "passive"))
      (node (ref "SWD") (pin "4") (pinfunction "4_4") (pintype "passive"))
      (node (ref "U2") (pin "23") (pinfunction "VSS_1_23") (pintype "power_in"))
      (node (ref "U2") (pin "35") (pinfunction "VSS_2_35") (pintype "power_in"))
      (node (ref "U2") (pin "44") (pinfunction "BOOT0_44") (pintype "input"))
      (node (ref "U2") (pin "47") (pinfunction "VSS_3_47") (pintype "power_in"))
      (node (ref "U2") (pin "8") (pinfunction "VSSA_8") (pintype "power_in"))
      (node (ref "UART") (pin "3") (pinfunction "3_3") (pintype "passive"))
      (node (ref "UART2") (pin "3") (pinfunction "3_3") (pintype "passive"))
      (node (ref "X0") (pin "14") (pinfunction "GND_14") (pintype "power_in"))
      (node (ref "X0") (pin "20") (pinfunction "GND_20") (pintype "power_in"))
      (node (ref "X0") (pin "25") (pinfunction "GND_25") (pintype "power_in"))
      (node (ref "X0") (pin "6") (pinfunction "GND_6") (pintype "power_in"))
      (node (ref "X0") (pin "9") (pinfunction "GND_9") (pintype "power_in"))
      (node (ref "X15") (pin "2") (pinfunction "KL_2") (pintype "passive"))
      (node (ref "X4") (pin "2") (pinfunction "KL_2") (pintype "passive"))
      (node (ref "X9") (pin "3") (pinfunction "KL_3") (pintype "passive"))
    )
    (net (code "29") (name "Net-(1W-1A-K)") (class "Default")
      (node (ref "1W-1") (pin "1") (pinfunction "K_1") (pintype "passive"))
      (node (ref "L1W1") (pin "A") (pinfunction "A_A") (pintype "passive"))
      (node (ref "Q8") (pin "3") (pinfunction "D_3") (pintype "passive"))
    )
    (net (code "30") (name "Net-(1W-1B-K)") (class "Default")
      (node (ref "1W-1") (pin "2") (pinfunction "K_2") (pintype "passive"))
      (node (ref "D15") (pin "3") (pinfunction "C1A2_3") (pintype "passive"))
      (node (ref "IC5") (pin "4") (pinfunction "X_4") (pintype "bidirectional"))
    )
    (net (code "31") (name "Net-(1W-2A-K)") (class "Default")
      (node (ref "1W-2") (pin "1") (pinfunction "K_1") (pintype "passive"))
      (node (ref "L1W2") (pin "A") (pinfunction "A_A") (pintype "passive"))
      (node (ref "Q10") (pin "3") (pinfunction "D_3") (pintype "passive"))
    )
    (net (code "32") (name "Net-(1W-2B-K)") (class "Default")
      (node (ref "1W-2") (pin "2") (pinfunction "K_2") (pintype "passive"))
      (node (ref "D16") (pin "3") (pinfunction "C1A2_3") (pintype "passive"))
      (node (ref "IC8") (pin "4") (pinfunction "X_4") (pintype "bidirectional"))
    )
    (net (code "33") (name "Net-(A0-P$1)") (class "Default")
      (node (ref "A0") (pin "2") (pinfunction "P$1_2") (pintype "bidirectional"))
      (node (ref "IC9") (pin "3") (pinfunction "A2_3") (pintype "input"))
    )
    (net (code "34") (name "Net-(C21-Pad+)") (class "Default")
      (node (ref "C21") (pin "+") (pinfunction "+_+") (pintype "passive"))
      (node (ref "K1") (pin "2") (pinfunction "2_2") (pintype "passive"))
      (node (ref "R26") (pin "2") (pinfunction "2_2") (pintype "passive"))
    )
    (net (code "35") (name "Net-(C25-Pad+)") (class "Default")
      (node (ref "C25") (pin "+") (pinfunction "+_+") (pintype "passive"))
      (node (ref "K6") (pin "2") (pinfunction "2_2") (pintype "passive"))
      (node (ref "R41") (pin "2") (pinfunction "2_2") (pintype "passive"))
    )
    (net (code "36") (name "Net-(IC1A-1W)") (class "Default")
      (node (ref "IC1") (pin "2") (pinfunction "1W_2") (pintype "open_collector"))
      (node (ref "IC5") (pin "3") (pinfunction "A_3") (pintype "bidirectional"))
      (node (ref "IC8") (pin "3") (pinfunction "A_3") (pintype "bidirectional"))
      (node (ref "Q7") (pin "3") (pinfunction "D_3") (pintype "passive"))
    )
    (net (code "37") (name "Net-(IC1A-PCT)") (class "Default")
      (node (ref "IC1") (pin "6") (pinfunction "PCT_6") (pintype "output"))
      (node (ref "Q7") (pin "1") (pinfunction "G_1") (pintype "passive"))
    )
    (net (code "38") (name "Net-(IC3-OUTF1)") (class "Default")
      (node (ref "IC3") (pin "5") (pinfunction "OUTF1_5") (pintype "bidirectional"))
      (node (ref "IC3") (pin "6") (pinfunction "OUTF2_6") (pintype "bidirectional"))
      (node (ref "X4") (pin "1") (pinfunction "KL_1") (pintype "passive"))
    )
    (net (code "39") (name "Net-(IC3-OUTR1)") (class "Default")
      (node (ref "IC3") (pin "7") (pinfunction "OUTR1_7") (pintype "bidirectional"))
      (node (ref "IC3") (pin "8") (pinfunction "OUTR2_8") (pintype "bidirectional"))
      (node (ref "X4") (pin "3") (pinfunction "KL_3") (pintype "passive"))
    )
    (net (code "40") (name "Net-(IC4-VO)") (class "Default")
      (node (ref "C17") (pin "2") (pinfunction "2_2") (pintype "passive"))
      (node (ref "C18") (pin "2") (pinfunction "2_2") (pintype "passive"))
      (node (ref "C23") (pin "+") (pinfunction "+_+") (pintype "passive"))
      (node (ref "C3") (pin "1") (pinfunction "1_1") (pintype "passive"))
      (node (ref "FB1") (pin "1") (pinfunction "1_1") (pintype "passive"))
      (node (ref "IC4") (pin "1") (pinfunction "VO_1") (pintype "passive"))
      (node (ref "R14") (pin "2") (pinfunction "2_2") (pintype "passive"))
      (node (ref "R8") (pin "2") (pinfunction "2_2") (pintype "passive"))
      (node (ref "SWD") (pin "1") (pinfunction "1_1") (pintype "passive"))
      (node (ref "U2") (pin "24") (pinfunction "VDD_1_24") (pintype "power_in"))
      (node (ref "U2") (pin "36") (pinfunction "VDD_2_36") (pintype "power_in"))
      (node (ref "U2") (pin "48") (pinfunction "VDD_3_48") (pintype "power_in"))
    )
    (net (code "41") (name "Net-(IC6-BST)") (class "Default")
      (node (ref "C8") (pin "1") (pinfunction "1_1") (pintype "passive"))
      (node (ref "IC6") (pin "6") (pinfunction "BST_6") (pintype "input"))
    )
    (net (code "42") (name "Net-(IC6-FB)") (class "Default")
      (node (ref "IC6") (pin "4") (pinfunction "FB_4") (pintype "input"))
      (node (ref "R10") (pin "2") (pinfunction "2_2") (pintype "passive"))
      (node (ref "R11") (pin "2") (pinfunction "2_2") (pintype "passive"))
    )
    (net (code "43") (name "Net-(IC6-SW)") (class "Default")
      (node (ref "C8") (pin "2") (pinfunction "2_2") (pintype "passive"))
      (node (ref "IC6") (pin "2") (pinfunction "SW_2") (pintype "passive"))
      (node (ref "L4.7") (pin "P$1") (pinfunction "1_P$1") (pintype "passive"))
    )
    (net (code "44") (name "Net-(IC9-P0)") (class "Default")
      (node (ref "IC9") (pin "4") (pinfunction "P0_4") (pintype "bidirectional"))
      (node (ref "R47") (pin "2") (pinfunction "2_2") (pintype "passive"))
      (node (ref "R62") (pin "1") (pinfunction "1_1") (pintype "passive"))
    )
    (net (code "45") (name "Net-(IC9-P1)") (class "Default")
      (node (ref "IC9") (pin "5") (pinfunction "P1_5") (pintype "bidirectional"))
      (node (ref "R44") (pin "2") (pinfunction "2_2") (pintype "passive"))
      (node (ref "R61") (pin "1") (pinfunction "1_1") (pintype "passive"))
    )
    (net (code "46") (name "Net-(IC9-P2)") (class "Default")
      (node (ref "IC9") (pin "6") (pinfunction "P2_6") (pintype "bidirectional"))
      (node (ref "R37") (pin "1") (pinfunction "1_1") (pintype "passive"))
      (node (ref "R84") (pin "2") (pinfunction "2_2") (pintype "passive"))
    )
    (net (code "47") (name "Net-(IC9-P3)") (class "Default")
      (node (ref "IC9") (pin "7") (pinfunction "P3_7") (pintype "bidirectional"))
      (node (ref "R73") (pin "1") (pinfunction "1_1") (pintype "passive"))
      (node (ref "R77") (pin "2") (pinfunction "2_2") (pintype "passive"))
    )
    (net (code "48") (name "Net-(IC9-P4)") (class "Default")
      (node (ref "IC9") (pin "9") (pinfunction "P4_9") (pintype "bidirectional"))
      (node (ref "R40") (pin "2") (pinfunction "2_2") (pintype "passive"))
      (node (ref "R59") (pin "1") (pinfunction "1_1") (pintype "passive"))
    )
    (net (code "49") (name "Net-(IC9-P5)") (class "Default")
      (node (ref "IC9") (pin "10") (pinfunction "P5_10") (pintype "bidirectional"))
      (node (ref "R43") (pin "2") (pinfunction "2_2") (pintype "passive"))
      (node (ref "R60") (pin "1") (pinfunction "1_1") (pintype "passive"))
    )
    (net (code "50") (name "Net-(IC10-OUTF1)") (class "Default")
      (node (ref "IC10") (pin "5") (pinfunction "OUTF1_5") (pintype "bidirectional"))
      (node (ref "IC10") (pin "6") (pinfunction "OUTF2_6") (pintype "bidirectional"))
      (node (ref "X15") (pin "1") (pinfunction "KL_1") (pintype "passive"))
    )
    (net (code "51") (name "Net-(IC10-OUTR1)") (class "Default")
      (node (ref "IC10") (pin "7") (pinfunction "OUTR1_7") (pintype "bidirectional"))
      (node (ref "IC10") (pin "8") (pinfunction "OUTR2_8") (pintype "bidirectional"))
      (node (ref "X15") (pin "3") (pinfunction "KL_3") (pintype "passive"))
    )
    (net (code "52") (name "Net-(K2A-PA)") (class "Default")
      (node (ref "K2") (pin "3") (pinfunction "PA_3") (pintype "passive"))
      (node (ref "K2") (pin "6") (pinfunction "PB_6") (pintype "passive"))
      (node (ref "X1") (pin "1") (pinfunction "KL_1") (pintype "passive"))
    )
    (net (code "53") (name "Net-(K2A-SA)") (class "Default")
      (node (ref "K2") (pin "4") (pinfunction "SA_4") (pintype "passive"))
      (node (ref "K2") (pin "5") (pinfunction "SB_5") (pintype "passive"))
      (node (ref "X1") (pin "2") (pinfunction "KL_2") (pintype "passive"))
    )
    (net (code "54") (name "Net-(K2B-2)") (class "Default")
      (node (ref "C27") (pin "+") (pinfunction "+_+") (pintype "passive"))
      (node (ref "K2") (pin "8") (pinfunction "2_8") (pintype "passive"))
      (node (ref "R74") (pin "2") (pinfunction "2_2") (pintype "passive"))
    )
    (net (code "55") (name "Net-(K3A-PA)") (class "Default")
      (node (ref "K3") (pin "3") (pinfunction "PA_3") (pintype "passive"))
      (node (ref "K3") (pin "6") (pinfunction "PB_6") (pintype "passive"))
      (node (ref "X2") (pin "1") (pinfunction "KL_1") (pintype "passive"))
    )
    (net (code "56") (name "Net-(K3A-SA)") (class "Default")
      (node (ref "K3") (pin "4") (pinfunction "SA_4") (pintype "passive"))
      (node (ref "K3") (pin "5") (pinfunction "SB_5") (pintype "passive"))
      (node (ref "X2") (pin "2") (pinfunction "KL_2") (pintype "passive"))
    )
    (net (code "57") (name "Net-(K3B-2)") (class "Default")
      (node (ref "C26") (pin "+") (pinfunction "+_+") (pintype "passive"))
      (node (ref "K3") (pin "8") (pinfunction "2_8") (pintype "passive"))
      (node (ref "R82") (pin "2") (pinfunction "2_2") (pintype "passive"))
    )
    (net (code "58") (name "Net-(L1W1-PadC)") (class "Default")
      (node (ref "L1W1") (pin "C") (pinfunction "C_C") (pintype "passive"))
      (node (ref "R76") (pin "1") (pinfunction "1_1") (pintype "passive"))
    )
    (net (code "59") (name "Net-(L1W2-PadC)") (class "Default")
      (node (ref "L1W2") (pin "C") (pinfunction "C_C") (pintype "passive"))
      (node (ref "R45") (pin "1") (pinfunction "1_1") (pintype "passive"))
    )
    (net (code "60") (name "Net-(L4.7-2)") (class "Default")
      (node (ref "C14") (pin "+") (pinfunction "+_+") (pintype "passive"))
      (node (ref "C22") (pin "2") (pinfunction "2_2") (pintype "passive"))
      (node (ref "C9") (pin "2") (pinfunction "2_2") (pintype "passive"))
      (node (ref "L4.7") (pin "P$2") (pinfunction "2_P$2") (pintype "passive"))
      (node (ref "R11") (pin "1") (pinfunction "1_1") (pintype "passive"))
      (node (ref "R5") (pin "2") (pinfunction "2_2") (pintype "passive"))
      (node (ref "X0") (pin "2") (pinfunction "5V_2") (pintype "power_in"))
      (node (ref "X0") (pin "4") (pinfunction "5V_4") (pintype "power_in"))
    )
    (net (code "61") (name "Net-(LED1-PadC)") (class "Default")
      (node (ref "LED1") (pin "C") (pinfunction "C_C") (pintype "passive"))
      (node (ref "R22") (pin "1") (pinfunction "1_1") (pintype "passive"))
    )
    (net (code "62") (name "Net-(LED2-PadC)") (class "Default")
      (node (ref "LED2") (pin "C") (pinfunction "C_C") (pintype "passive"))
      (node (ref "R23") (pin "1") (pinfunction "1_1") (pintype "passive"))
    )
    (net (code "63") (name "Net-(LED3-PadC)") (class "Default")
      (node (ref "LED3") (pin "C") (pinfunction "C_C") (pintype "passive"))
      (node (ref "R75") (pin "1") (pinfunction "1_1") (pintype "passive"))
    )
    (net (code "64") (name "Net-(LED4-PadC)") (class "Default")
      (node (ref "LED4") (pin "C") (pinfunction "C_C") (pintype "passive"))
      (node (ref "R83") (pin "1") (pinfunction "1_1") (pintype "passive"))
    )
    (net (code "65") (name "Net-(LED7-PadC)") (class "Default")
      (node (ref "LED7") (pin "C") (pinfunction "C_C") (pintype "passive"))
      (node (ref "R36") (pin "1") (pinfunction "1_1") (pintype "passive"))
    )
    (net (code "66") (name "Net-(LED8-PadC)") (class "Default")
      (node (ref "LED8") (pin "C") (pinfunction "C_C") (pintype "passive"))
      (node (ref "R42") (pin "1") (pinfunction "1_1") (pintype "passive"))
    )
    (net (code "67") (name "Net-(LED9-PadC)") (class "Default")
      (node (ref "LED9") (pin "C") (pinfunction "C_C") (pintype "passive"))
      (node (ref "R25") (pin "1") (pinfunction "1_1") (pintype "passive"))
    )
    (net (code "68") (name "Net-(LED10-PadC)") (class "Default")
      (node (ref "LED10") (pin "C") (pinfunction "C_C") (pintype "passive"))
      (node (ref "R64") (pin "1") (pinfunction "1_1") (pintype "passive"))
    )
    (net (code "69") (name "Net-(Q1-D)") (class "Default")
      (node (ref "D3") (pin "A") (pinfunction "A_A") (pintype "passive"))
      (node (ref "Q1") (pin "3") (pinfunction "D_3") (pintype "passive"))
      (node (ref "Q9") (pin "5") (pinfunction "D_5") (pintype "passive"))
      (node (ref "Q9") (pin "6") (pinfunction "D_6") (pintype "passive"))
      (node (ref "Q9") (pin "7") (pinfunction "D_7") (pintype "passive"))
      (node (ref "Q9") (pin "8") (pinfunction "D_8") (pintype "passive"))
      (node (ref "R25") (pin "2") (pinfunction "2_2") (pintype "passive"))
      (node (ref "X10") (pin "2") (pinfunction "KL_2") (pintype "passive"))
    )
    (net (code "70") (name "Net-(Q1-G)") (class "Default")
      (node (ref "Q1") (pin "1") (pinfunction "G_1") (pintype "passive"))
      (node (ref "Q9") (pin "4") (pinfunction "G_4") (pintype "passive"))
      (node (ref "R44") (pin "1") (pinfunction "1_1") (pintype "passive"))
    )
    (net (code "71") (name "Net-(Q2-D)") (class "Default")
      (node (ref "Q2") (pin "3") (pinfunction "D_3") (pintype "passive"))
      (node (ref "R28") (pin "1") (pinfunction "1_1") (pintype "passive"))
    )
    (net (code "72") (name "Net-(Q2-G)") (class "Default")
      (node (ref "Q2") (pin "1") (pinfunction "G_1") (pintype "passive"))
      (node (ref "R71") (pin "2") (pinfunction "2_2") (pintype "passive"))
    )
    (net (code "73") (name "Net-(Q3-D)") (class "Default")
      (node (ref "D1") (pin "A") (pinfunction "A_A") (pintype "passive"))
      (node (ref "K1") (pin "1") (pinfunction "1_1") (pintype "passive"))
      (node (ref "Q3") (pin "3") (pinfunction "D_3") (pintype "passive"))
      (node (ref "R36") (pin "2") (pinfunction "2_2") (pintype "passive"))
    )
    (net (code "74") (name "Net-(Q3-G)") (class "Default")
      (node (ref "Q3") (pin "1") (pinfunction "G_1") (pintype "passive"))
      (node (ref "R40") (pin "1") (pinfunction "1_1") (pintype "passive"))
    )
    (net (code "75") (name "Net-(Q4-D)") (class "Default")
      (node (ref "D2") (pin "A") (pinfunction "A_A") (pintype "passive"))
      (node (ref "K6") (pin "1") (pinfunction "1_1") (pintype "passive"))
      (node (ref "Q4") (pin "3") (pinfunction "D_3") (pintype "passive"))
      (node (ref "R42") (pin "2") (pinfunction "2_2") (pintype "passive"))
    )
    (net (code "76") (name "Net-(Q4-G)") (class "Default")
      (node (ref "Q4") (pin "1") (pinfunction "G_1") (pintype "passive"))
      (node (ref "R43") (pin "1") (pinfunction "1_1") (pintype "passive"))
    )
    (net (code "77") (name "Net-(Q5-D)") (class "Default")
      (node (ref "D4") (pin "A") (pinfunction "A_A") (pintype "passive"))
      (node (ref "Q11") (pin "5") (pinfunction "D_5") (pintype "passive"))
      (node (ref "Q11") (pin "6") (pinfunction "D_6") (pintype "passive"))
      (node (ref "Q11") (pin "7") (pinfunction "D_7") (pintype "passive"))
      (node (ref "Q11") (pin "8") (pinfunction "D_8") (pintype "passive"))
      (node (ref "Q5") (pin "3") (pinfunction "D_3") (pintype "passive"))
      (node (ref "R64") (pin "2") (pinfunction "2_2") (pintype "passive"))
      (node (ref "X11") (pin "2") (pinfunction "KL_2") (pintype "passive"))
    )
    (net (code "78") (name "Net-(Q8-G)") (class "Default")
      (node (ref "Q8") (pin "1") (pinfunction "G_1") (pintype "passive"))
      (node (ref "R31") (pin "2") (pinfunction "2_2") (pintype "passive"))
    )
    (net (code "79") (name "Net-(Q10-G)") (class "Default")
      (node (ref "Q10") (pin "1") (pinfunction "G_1") (pintype "passive"))
      (node (ref "R32") (pin "2") (pinfunction "2_2") (pintype "passive"))
    )
    (net (code "80") (name "Net-(Q11-G)") (class "Default")
      (node (ref "Q11") (pin "4") (pinfunction "G_4") (pintype "passive"))
      (node (ref "Q5") (pin "1") (pinfunction "G_1") (pintype "passive"))
      (node (ref "R47") (pin "1") (pinfunction "1_1") (pintype "passive"))
    )
    (net (code "81") (name "Net-(Q13-D)") (class "Default")
      (node (ref "D19") (pin "A") (pinfunction "A_A") (pintype "passive"))
      (node (ref "K2") (pin "1") (pinfunction "1_1") (pintype "passive"))
      (node (ref "Q13") (pin "3") (pinfunction "D_3") (pintype "passive"))
      (node (ref "R75") (pin "2") (pinfunction "2_2") (pintype "passive"))
    )
    (net (code "82") (name "Net-(Q13-G)") (class "Default")
      (node (ref "Q13") (pin "1") (pinfunction "G_1") (pintype "passive"))
      (node (ref "R77") (pin "1") (pinfunction "1_1") (pintype "passive"))
    )
    (net (code "83") (name "Net-(Q14-D)") (class "Default")
      (node (ref "D21") (pin "A") (pinfunction "A_A") (pintype "passive"))
      (node (ref "K3") (pin "1") (pinfunction "1_1") (pintype "passive"))
      (node (ref "Q14") (pin "3") (pinfunction "D_3") (pintype "passive"))
      (node (ref "R83") (pin "2") (pinfunction "2_2") (pintype "passive"))
    )
    (net (code "84") (name "Net-(Q14-G)") (class "Default")
      (node (ref "Q14") (pin "1") (pinfunction "G_1") (pintype "passive"))
      (node (ref "R84") (pin "1") (pinfunction "1_1") (pintype "passive"))
    )
    (net (code "85") (name "Net-(U2-VBAT)") (class "Default")
      (node (ref "C2") (pin "1") (pinfunction "1_1") (pintype "passive"))
      (node (ref "FB1") (pin "2") (pinfunction "2_2") (pintype "passive"))
      (node (ref "U2") (pin "1") (pinfunction "VBAT_1") (pintype "power_in"))
      (node (ref "U2") (pin "9") (pinfunction "VDDA_9") (pintype "power_in"))
    )
    (net (code "86") (name "Net-(X0-PWM1{slash}PA06)") (class "Default")
      (node (ref "R70") (pin "1") (pinfunction "1_1") (pintype "passive"))
      (node (ref "R71") (pin "1") (pinfunction "1_1") (pintype "passive"))
      (node (ref "X0") (pin "7") (pinfunction "PWM1/PA06_7") (pintype "bidirectional"))
    )
    (net (code "87") (name "Net-(X0-UART1_RX{slash}PG07)") (class "Default")
      (node (ref "R1") (pin "2") (pinfunction "2_2") (pintype "passive"))
      (node (ref "R3") (pin "2") (pinfunction "2_2") (pintype "passive"))
      (node (ref "UART") (pin "2") (pinfunction "2_2") (pintype "passive"))
      (node (ref "X0") (pin "10") (pinfunction "UART1_RX/PG07_10") (pintype "bidirectional"))
    )
    (net (code "88") (name "Net-(X0-UART1_TX{slash}PG06)") (class "Default")
      (node (ref "R2") (pin "2") (pinfunction "2_2") (pintype "passive"))
      (node (ref "R4") (pin "2") (pinfunction "2_2") (pintype "passive"))
      (node (ref "UART") (pin "1") (pinfunction "1_1") (pintype "passive"))
      (node (ref "X0") (pin "8") (pinfunction "UART1_TX/PG06_8") (pintype "bidirectional"))
    )
    (net (code "89") (name "Net-(X0-UART2_RX{slash}PA01)") (class "Default")
      (node (ref "UART2") (pin "2") (pinfunction "2_2") (pintype "passive"))
      (node (ref "X0") (pin "11") (pinfunction "UART2_RX/PA01_11") (pintype "bidirectional"))
    )
    (net (code "90") (name "Net-(X0-UART2_TX{slash}PA00)") (class "Default")
      (node (ref "UART2") (pin "1") (pinfunction "1_1") (pintype "passive"))
      (node (ref "X0") (pin "13") (pinfunction "UART2_TX/PA00_13") (pintype "bidirectional"))
    )
    (net (code "91") (name "Net-(X6A-KL)") (class "Default")
      (node (ref "K1") (pin "O") (pinfunction "O_O") (pintype "passive"))
      (node (ref "X6") (pin "1") (pinfunction "KL_1") (pintype "passive"))
    )
    (net (code "92") (name "Net-(X6B-KL)") (class "Default")
      (node (ref "K1") (pin "P") (pinfunction "P_P") (pintype "passive"))
      (node (ref "X6") (pin "2") (pinfunction "KL_2") (pintype "passive"))
    )
    (net (code "93") (name "Net-(X6C-KL)") (class "Default")
      (node (ref "K1") (pin "S") (pinfunction "S_S") (pintype "passive"))
      (node (ref "X6") (pin "3") (pinfunction "KL_3") (pintype "passive"))
    )
    (net (code "94") (name "Net-(X8A-KL)") (class "Default")
      (node (ref "K6") (pin "O") (pinfunction "O_O") (pintype "passive"))
      (node (ref "X8") (pin "1") (pinfunction "KL_1") (pintype "passive"))
    )
    (net (code "95") (name "Net-(X8B-KL)") (class "Default")
      (node (ref "K6") (pin "P") (pinfunction "P_P") (pintype "passive"))
      (node (ref "X8") (pin "2") (pinfunction "KL_2") (pintype "passive"))
    )
    (net (code "96") (name "Net-(X8C-KL)") (class "Default")
      (node (ref "K6") (pin "S") (pinfunction "S_S") (pintype "passive"))
      (node (ref "X8") (pin "3") (pinfunction "KL_3") (pintype "passive"))
    )
    (net (code "97") (name "Net-(X9A-KL)") (class "Default")
      (node (ref "D10") (pin "A") (pinfunction "A_A") (pintype "passive"))
      (node (ref "R30") (pin "1") (pinfunction "1_1") (pintype "passive"))
      (node (ref "X9") (pin "1") (pinfunction "KL_1") (pintype "passive"))
    )
    (net (code "98") (name "VDD") (class "Default")
      (node (ref "C20") (pin "1") (pinfunction "1_1") (pintype "passive"))
      (node (ref "C24") (pin "1") (pinfunction "1_1") (pintype "passive"))
      (node (ref "C4") (pin "1") (pinfunction "1_1") (pintype "passive"))
      (node (ref "C7") (pin "1") (pinfunction "1_1") (pintype "passive"))
      (node (ref "D14") (pin "C") (pinfunction "C_C") (pintype "passive"))
      (node (ref "D15") (pin "2") (pinfunction "C2_2") (pintype "passive"))
      (node (ref "D16") (pin "2") (pinfunction "C2_2") (pintype "passive"))
      (node (ref "DD1") (pin "2") (pinfunction "VDD_2") (pintype "input"))
      (node (ref "IC2") (pin "3") (pinfunction "VI_3") (pintype "input"))
      (node (ref "LED1") (pin "A") (pinfunction "A_A") (pintype "passive"))
      (node (ref "LED2") (pin "A") (pinfunction "A_A") (pintype "passive"))
      (node (ref "Q10") (pin "2") (pinfunction "S_2") (pintype "passive"))
      (node (ref "Q7") (pin "2") (pinfunction "S_2") (pintype "passive"))
      (node (ref "Q8") (pin "2") (pinfunction "S_2") (pintype "passive"))
      (node (ref "R27") (pin "2") (pinfunction "2_2") (pintype "passive"))
      (node (ref "R38") (pin "2") (pinfunction "2_2") (pintype "passive"))
      (node (ref "R39") (pin "2") (pinfunction "2_2") (pintype "passive"))
    )
    (net (code "99") (name "unconnected-(IC7-NC-Pad3)") (class "Default")
      (node (ref "IC7") (pin "3") (pinfunction "NC_3") (pintype "no_connect"))
    )
    (net (code "100") (name "unconnected-(IC9-~{INT}-Pad13)") (class "Default")
      (node (ref "IC9") (pin "13") (pinfunction "~{INT}_13") (pintype "output"))
    )
    (net (code "101") (name "unconnected-(K2A-OA-Pad2)") (class "Default")
      (node (ref "K2") (pin "2") (pinfunction "OA_2") (pintype "passive"))
    )
    (net (code "102") (name "unconnected-(K2A-OB-Pad7)") (class "Default")
      (node (ref "K2") (pin "7") (pinfunction "OB_7") (pintype "passive"))
    )
    (net (code "103") (name "unconnected-(K3A-OA-Pad2)") (class "Default")
      (node (ref "K3") (pin "2") (pinfunction "OA_2") (pintype "passive"))
    )
    (net (code "104") (name "unconnected-(K3A-OB-Pad7)") (class "Default")
      (node (ref "K3") (pin "7") (pinfunction "OB_7") (pintype "passive"))
    )
    (net (code "105") (name "unconnected-(U2-PA4-Pad14)") (class "Default")
      (node (ref "U2") (pin "14") (pinfunction "PA4_14") (pintype "bidirectional"))
    )
    (net (code "106") (name "unconnected-(U2-PA5-Pad15)") (class "Default")
      (node (ref "U2") (pin "15") (pinfunction "PA5_15") (pintype "bidirectional"))
    )
    (net (code "107") (name "unconnected-(U2-PA6-Pad16)") (class "Default")
      (node (ref "U2") (pin "16") (pinfunction "PA6_16") (pintype "bidirectional"))
    )
    (net (code "108") (name "unconnected-(U2-PA7-Pad17)") (class "Default")
      (node (ref "U2") (pin "17") (pinfunction "PA7_17") (pintype "bidirectional"))
    )
    (net (code "109") (name "unconnected-(U2-PA8-Pad29)") (class "Default")
      (node (ref "U2") (pin "29") (pinfunction "PA8_29") (pintype "bidirectional"))
    )
    (net (code "110") (name "unconnected-(U2-PA15-Pad38)") (class "Default")
      (node (ref "U2") (pin "38") (pinfunction "PA15_38") (pintype "bidirectional"))
    )
    (net (code "111") (name "unconnected-(U2-PB0-Pad18)") (class "Default")
      (node (ref "U2") (pin "18") (pinfunction "PB0_18") (pintype "bidirectional"))
    )
    (net (code "112") (name "unconnected-(U2-PB1-Pad19)") (class "Default")
      (node (ref "U2") (pin "19") (pinfunction "PB1_19") (pintype "bidirectional"))
    )
    (net (code "113") (name "unconnected-(U2-PB2-Pad20)") (class "Default")
      (node (ref "U2") (pin "20") (pinfunction "PB2_20") (pintype "bidirectional"))
    )
    (net (code "114") (name "unconnected-(U2-PB5-Pad41)") (class "Default")
      (node (ref "U2") (pin "41") (pinfunction "PB5_41") (pintype "bidirectional"))
    )
    (net (code "115") (name "unconnected-(U2-PB10-Pad21)") (class "Default")
      (node (ref "U2") (pin "21") (pinfunction "PB10_21") (pintype "bidirectional"))
    )
    (net (code "116") (name "unconnected-(U2-PB11-Pad22)") (class "Default")
      (node (ref "U2") (pin "22") (pinfunction "PB11_22") (pintype "bidirectional"))
    )
    (net (code "117") (name "unconnected-(U2-PB12-Pad25)") (class "Default")
      (node (ref "U2") (pin "25") (pinfunction "PB12_25") (pintype "bidirectional"))
    )
    (net (code "118") (name "unconnected-(U2-PB13-Pad26)") (class "Default")
      (node (ref "U2") (pin "26") (pinfunction "PB13_26") (pintype "bidirectional"))
    )
    (net (code "119") (name "unconnected-(U2-PC14-OSC32_IN-Pad3)") (class "Default")
      (node (ref "U2") (pin "3") (pinfunction "PC14-OSC32_IN_3") (pintype "bidirectional"))
    )
    (net (code "120") (name "unconnected-(U2-PC15-OSC32_OUT-Pad4)") (class "Default")
      (node (ref "U2") (pin "4") (pinfunction "PC15-OSC32_OUT_4") (pintype "bidirectional"))
    )
    (net (code "121") (name "unconnected-(U2-PD0-OSC_IN-Pad5)") (class "Default")
      (node (ref "U2") (pin "5") (pinfunction "PD0-OSC_IN_5") (pintype "input"))
    )
    (net (code "122") (name "unconnected-(U2-PD1-OSC_OUT-Pad6)") (class "Default")
      (node (ref "U2") (pin "6") (pinfunction "PD1-OSC_OUT_6") (pintype "output"))
    )
    (net (code "123") (name "unconnected-(X0-PA13{slash}SPI1_CS-Pad24)") (class "Default")
      (node (ref "X0") (pin "24") (pinfunction "PA13/SPI1_CS_24") (pintype "bidirectional"))
    )
    (net (code "124") (name "unconnected-(X0-PA14{slash}SPI1_CLK-Pad23)") (class "Default")
      (node (ref "X0") (pin "23") (pinfunction "PA14/SPI1_CLK_23") (pintype "bidirectional"))
    )
    (net (code "125") (name "unconnected-(X0-PA15{slash}SPI1_MOSI-Pad19)") (class "Default")
      (node (ref "X0") (pin "19") (pinfunction "PA15/SPI1_MOSI_19") (pintype "bidirectional"))
    )
    (net (code "126") (name "unconnected-(X0-PA16{slash}SPI1_MISO-Pad21)") (class "Default")
      (node (ref "X0") (pin "21") (pinfunction "PA16/SPI1_MISO_21") (pintype "bidirectional"))
    )
    (net (code "127") (name "unconnected-(X0-PA18{slash}TWI1_SCL-Pad18)") (class "Default")
      (node (ref "X0") (pin "18") (pinfunction "PA18/TWI1_SCL_18") (pintype "bidirectional"))
    )
    (net (code "128") (name "unconnected-(X0-PA19{slash}TWI1_SDA-Pad16)") (class "Default")
      (node (ref "X0") (pin "16") (pinfunction "PA19/TWI1_SDA_16") (pintype "bidirectional"))
    )
    (net (code "129") (name "unconnected-(X0-SIM_DET{slash}PA_EINT10{slash}PA10-Pad26)") (class "Default")
      (node (ref "X0") (pin "26") (pinfunction "SIM_DET/PA_EINT10/PA10_26") (pintype "bidirectional"))
    )
    (net (code "130") (name "unconnected-(X0-UART2_CTS{slash}PA03-Pad15)") (class "Default")
      (node (ref "X0") (pin "15") (pinfunction "UART2_CTS/PA03_15") (pintype "bidirectional"))
    )
    (net (code "131") (name "unconnected-(X0-UART2_RTS{slash}PA02-Pad22)") (class "Default")
      (node (ref "X0") (pin "22") (pinfunction "UART2_RTS/PA02_22") (pintype "bidirectional"))
    )
  )
)
